# EnguinoAuxDisplaySchematic.net
KiCad netlist of a schematic drawn in EAGLE
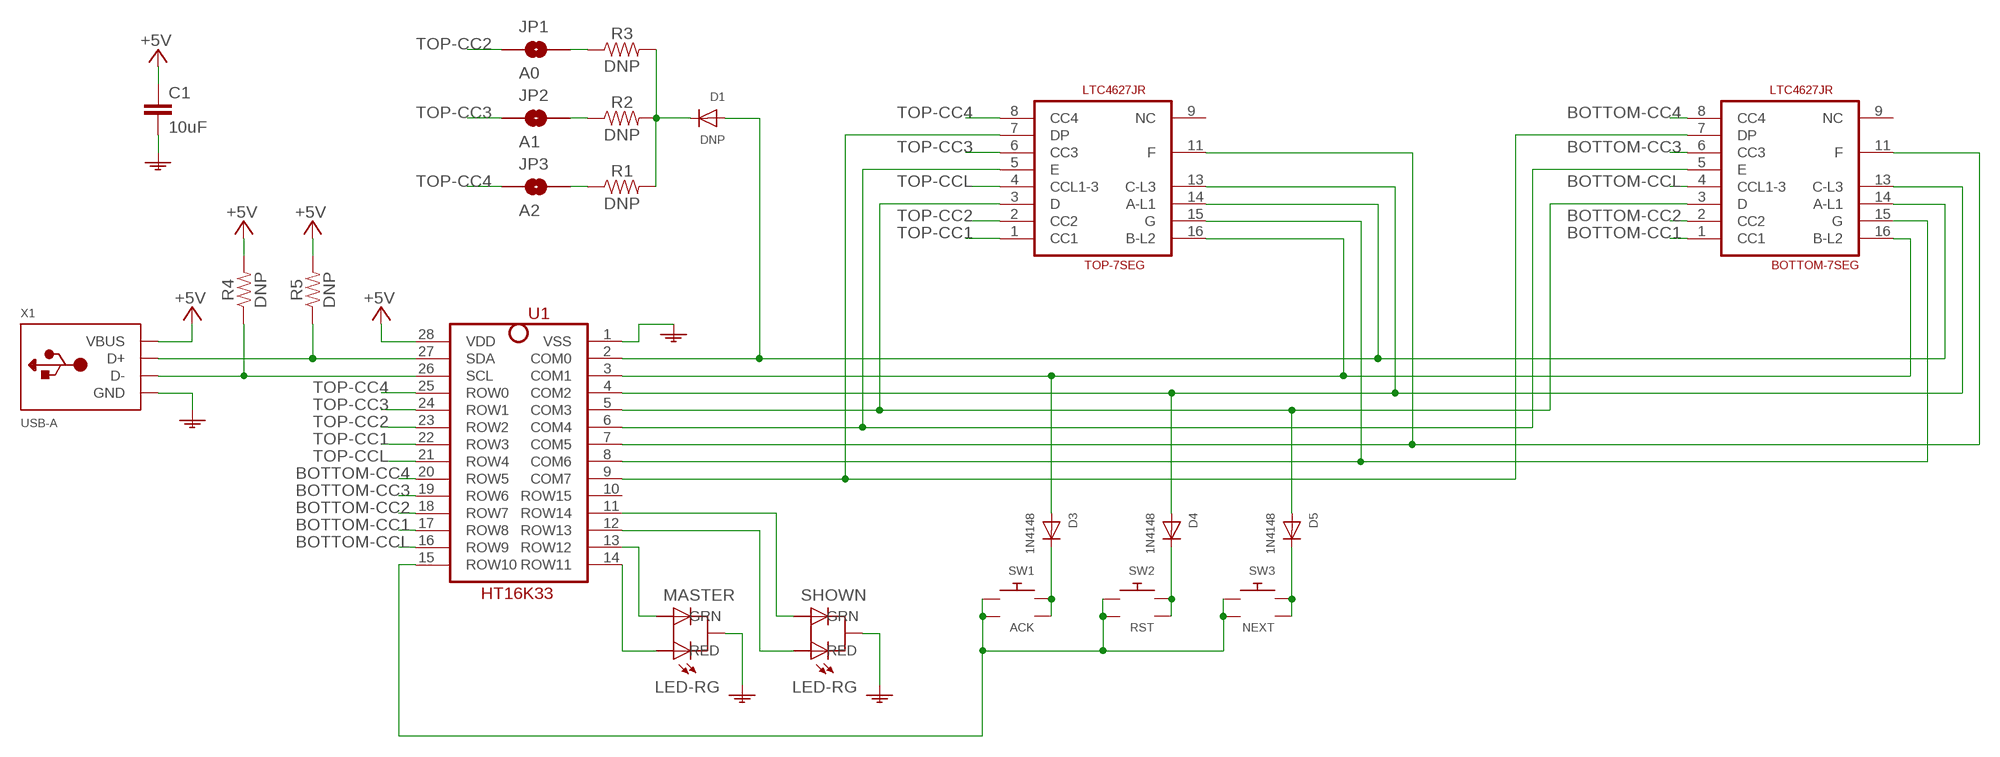
[diagram p0: schematic, sheet 1]

(export (version "E")
  (design (tool "Eeschema 10.0.6"))
  (components
    (comp (ref "BOTTOM-7SEG")
      (value "LTC4627JR")
      (footprint "eagle-import:7SEG-LED")
      (libsource (lib "eagle-import") (part "LTC4627JR"))
    )
    (comp (ref "C1")
      (value "10uF")
      (footprint "eagle-import:0805")
      (libsource (lib "eagle-import") (part "10UF-0805-10V-10%"))
    )
    (comp (ref "D1")
      (value "DNP")
      (footprint "eagle-import:SOD-123")
      (libsource (lib "eagle-import") (part "DIODESOD-123"))
    )
    (comp (ref "D3")
      (value "1N4148")
      (footprint "eagle-import:SOD-123")
      (libsource (lib "eagle-import") (part "DIODESOD-123"))
    )
    (comp (ref "D4")
      (value "1N4148")
      (footprint "eagle-import:SOD-123")
      (libsource (lib "eagle-import") (part "DIODESOD-123"))
    )
    (comp (ref "D5")
      (value "1N4148")
      (footprint "eagle-import:SOD-123")
      (libsource (lib "eagle-import") (part "DIODESOD-123"))
    )
    (comp (ref "JP1")
      (value "A0")
      (footprint "eagle-import:SMT-JUMPER_2_NO_SILK")
      (libsource (lib "eagle-import") (part "JUMPER-SMT_2_NO_SILK"))
    )
    (comp (ref "JP2")
      (value "A1")
      (footprint "eagle-import:SMT-JUMPER_2_NO_SILK")
      (libsource (lib "eagle-import") (part "JUMPER-SMT_2_NO_SILK"))
    )
    (comp (ref "JP3")
      (value "A2")
      (footprint "eagle-import:SMT-JUMPER_2_NO_SILK")
      (libsource (lib "eagle-import") (part "JUMPER-SMT_2_NO_SILK"))
    )
    (comp (ref "MASTER")
      (value "LED-RG")
      (footprint "eagle-import:LED-2-5MM")
      (libsource (lib "eagle-import") (part "LED-RG"))
    )
    (comp (ref "R1")
      (value "DNP")
      (footprint "eagle-import:0603")
      (libsource (lib "eagle-import") (part "47KOHM-0603-1/10W-1%"))
    )
    (comp (ref "R2")
      (value "DNP")
      (footprint "eagle-import:0603")
      (libsource (lib "eagle-import") (part "47KOHM-0603-1/10W-1%"))
    )
    (comp (ref "R3")
      (value "DNP")
      (footprint "eagle-import:0603")
      (libsource (lib "eagle-import") (part "47KOHM-0603-1/10W-1%"))
    )
    (comp (ref "R4")
      (value "DNP")
      (footprint "eagle-import:0603")
      (libsource (lib "eagle-import") (part "22KOHM-0603-1/10W-1%"))
    )
    (comp (ref "R5")
      (value "DNP")
      (footprint "eagle-import:0603")
      (libsource (lib "eagle-import") (part "22KOHM-0603-1/10W-1%"))
    )
    (comp (ref "SHOWN")
      (value "LED-RG")
      (footprint "eagle-import:LED-2-5MM")
      (libsource (lib "eagle-import") (part "LED-RG"))
    )
    (comp (ref "SW1")
      (value "ACK")
      (footprint "eagle-import:BUTTON-TH")
      (libsource (lib "eagle-import") (part "PUSHBUTTON"))
    )
    (comp (ref "SW2")
      (value "RST")
      (footprint "eagle-import:BUTTON-TH")
      (libsource (lib "eagle-import") (part "PUSHBUTTON"))
    )
    (comp (ref "SW3")
      (value "NEXT")
      (footprint "eagle-import:BUTTON-TH")
      (libsource (lib "eagle-import") (part "PUSHBUTTON"))
    )
    (comp (ref "TOP-7SEG")
      (value "LTC4627JR")
      (footprint "eagle-import:7SEG-LED")
      (libsource (lib "eagle-import") (part "LTC4627JR"))
    )
    (comp (ref "U1")
      (value "HT16K33")
      (footprint "eagle-import:SOP28")
      (libsource (lib "eagle-import") (part "HT16K33"))
    )
    (comp (ref "X1")
      (value "USB-A")
      (footprint "eagle-import:USB-A-AMPHENOL")
      (libsource (lib "eagle-import") (part "USB-A"))
    )
  )
  (nets
    (net (code "1") (name "+5V") (class "Default")
      (node (ref "C1") (pin "1") (pinfunction "1_1") (pintype "passive"))
      (node (ref "R4") (pin "2") (pinfunction "2_2") (pintype "passive"))
      (node (ref "R5") (pin "2") (pinfunction "2_2") (pintype "passive"))
      (node (ref "U1") (pin "28") (pinfunction "VDD_28") (pintype "power_in"))
      (node (ref "X1") (pin "P$1") (pinfunction "VBUS_P$1") (pintype "power_in"))
    )
    (net (code "2") (name "/BOTTOM-CC1") (class "Default")
      (node (ref "BOTTOM-7SEG") (pin "1") (pinfunction "CC1_1") (pintype "bidirectional"))
      (node (ref "U1") (pin "17") (pinfunction "ROW8_17") (pintype "bidirectional"))
    )
    (net (code "3") (name "/BOTTOM-CC2") (class "Default")
      (node (ref "BOTTOM-7SEG") (pin "2") (pinfunction "CC2_2") (pintype "bidirectional"))
      (node (ref "U1") (pin "18") (pinfunction "ROW7_18") (pintype "bidirectional"))
    )
    (net (code "4") (name "/BOTTOM-CC3") (class "Default")
      (node (ref "BOTTOM-7SEG") (pin "6") (pinfunction "CC3_6") (pintype "bidirectional"))
      (node (ref "U1") (pin "19") (pinfunction "ROW6_19") (pintype "bidirectional"))
    )
    (net (code "5") (name "/BOTTOM-CC4") (class "Default")
      (node (ref "BOTTOM-7SEG") (pin "8") (pinfunction "CC4_8") (pintype "bidirectional"))
      (node (ref "U1") (pin "20") (pinfunction "ROW5_20") (pintype "bidirectional"))
    )
    (net (code "6") (name "/BOTTOM-CCL") (class "Default")
      (node (ref "BOTTOM-7SEG") (pin "4") (pinfunction "CCL1-3_4") (pintype "bidirectional"))
      (node (ref "U1") (pin "16") (pinfunction "ROW9_16") (pintype "bidirectional"))
    )
    (net (code "7") (name "/TOP-CC1") (class "Default")
      (node (ref "TOP-7SEG") (pin "1") (pinfunction "CC1_1") (pintype "bidirectional"))
      (node (ref "U1") (pin "22") (pinfunction "ROW3_22") (pintype "bidirectional"))
    )
    (net (code "8") (name "/TOP-CC2") (class "Default")
      (node (ref "JP1") (pin "1") (pinfunction "1_1") (pintype "passive"))
      (node (ref "TOP-7SEG") (pin "2") (pinfunction "CC2_2") (pintype "bidirectional"))
      (node (ref "U1") (pin "23") (pinfunction "ROW2_23") (pintype "bidirectional"))
    )
    (net (code "9") (name "/TOP-CC3") (class "Default")
      (node (ref "JP2") (pin "1") (pinfunction "1_1") (pintype "passive"))
      (node (ref "TOP-7SEG") (pin "6") (pinfunction "CC3_6") (pintype "bidirectional"))
      (node (ref "U1") (pin "24") (pinfunction "ROW1_24") (pintype "bidirectional"))
    )
    (net (code "10") (name "/TOP-CC4") (class "Default")
      (node (ref "JP3") (pin "1") (pinfunction "1_1") (pintype "passive"))
      (node (ref "TOP-7SEG") (pin "8") (pinfunction "CC4_8") (pintype "bidirectional"))
      (node (ref "U1") (pin "25") (pinfunction "ROW0_25") (pintype "bidirectional"))
    )
    (net (code "11") (name "/TOP-CCL") (class "Default")
      (node (ref "TOP-7SEG") (pin "4") (pinfunction "CCL1-3_4") (pintype "bidirectional"))
      (node (ref "U1") (pin "21") (pinfunction "ROW4_21") (pintype "bidirectional"))
    )
    (net (code "12") (name "0V") (class "Default")
      (node (ref "C1") (pin "2") (pinfunction "2_2") (pintype "passive"))
      (node (ref "MASTER") (pin "2") (pinfunction "CC_2") (pintype "passive"))
      (node (ref "SHOWN") (pin "2") (pinfunction "CC_2") (pintype "passive"))
      (node (ref "U1") (pin "1") (pinfunction "VSS_1") (pintype "power_in"))
      (node (ref "X1") (pin "P$4") (pinfunction "GND_P$4") (pintype "power_in"))
    )
    (net (code "13") (name "Net-(BOTTOM-7SEG-A-L1)") (class "Default")
      (node (ref "BOTTOM-7SEG") (pin "14") (pinfunction "A-L1_14") (pintype "bidirectional"))
      (node (ref "D1") (pin "A") (pinfunction "A_A") (pintype "passive"))
      (node (ref "TOP-7SEG") (pin "14") (pinfunction "A-L1_14") (pintype "bidirectional"))
      (node (ref "U1") (pin "2") (pinfunction "COM0_2") (pintype "bidirectional"))
    )
    (net (code "14") (name "Net-(BOTTOM-7SEG-B-L2)") (class "Default")
      (node (ref "BOTTOM-7SEG") (pin "16") (pinfunction "B-L2_16") (pintype "bidirectional"))
      (node (ref "D3") (pin "A") (pinfunction "A_A") (pintype "passive"))
      (node (ref "TOP-7SEG") (pin "16") (pinfunction "B-L2_16") (pintype "bidirectional"))
      (node (ref "U1") (pin "3") (pinfunction "COM1_3") (pintype "bidirectional"))
    )
    (net (code "15") (name "Net-(BOTTOM-7SEG-C-L3)") (class "Default")
      (node (ref "BOTTOM-7SEG") (pin "13") (pinfunction "C-L3_13") (pintype "bidirectional"))
      (node (ref "D4") (pin "A") (pinfunction "A_A") (pintype "passive"))
      (node (ref "TOP-7SEG") (pin "13") (pinfunction "C-L3_13") (pintype "bidirectional"))
      (node (ref "U1") (pin "4") (pinfunction "COM2_4") (pintype "bidirectional"))
    )
    (net (code "16") (name "Net-(BOTTOM-7SEG-D)") (class "Default")
      (node (ref "BOTTOM-7SEG") (pin "3") (pinfunction "D_3") (pintype "bidirectional"))
      (node (ref "D5") (pin "A") (pinfunction "A_A") (pintype "passive"))
      (node (ref "TOP-7SEG") (pin "3") (pinfunction "D_3") (pintype "bidirectional"))
      (node (ref "U1") (pin "5") (pinfunction "COM3_5") (pintype "bidirectional"))
    )
    (net (code "17") (name "Net-(BOTTOM-7SEG-DP)") (class "Default")
      (node (ref "BOTTOM-7SEG") (pin "7") (pinfunction "DP_7") (pintype "bidirectional"))
      (node (ref "TOP-7SEG") (pin "7") (pinfunction "DP_7") (pintype "bidirectional"))
      (node (ref "U1") (pin "9") (pinfunction "COM7_9") (pintype "bidirectional"))
    )
    (net (code "18") (name "Net-(BOTTOM-7SEG-E)") (class "Default")
      (node (ref "BOTTOM-7SEG") (pin "5") (pinfunction "E_5") (pintype "bidirectional"))
      (node (ref "TOP-7SEG") (pin "5") (pinfunction "E_5") (pintype "bidirectional"))
      (node (ref "U1") (pin "6") (pinfunction "COM4_6") (pintype "bidirectional"))
    )
    (net (code "19") (name "Net-(BOTTOM-7SEG-F)") (class "Default")
      (node (ref "BOTTOM-7SEG") (pin "11") (pinfunction "F_11") (pintype "bidirectional"))
      (node (ref "TOP-7SEG") (pin "11") (pinfunction "F_11") (pintype "bidirectional"))
      (node (ref "U1") (pin "7") (pinfunction "COM5_7") (pintype "bidirectional"))
    )
    (net (code "20") (name "Net-(BOTTOM-7SEG-G)") (class "Default")
      (node (ref "BOTTOM-7SEG") (pin "15") (pinfunction "G_15") (pintype "bidirectional"))
      (node (ref "TOP-7SEG") (pin "15") (pinfunction "G_15") (pintype "bidirectional"))
      (node (ref "U1") (pin "8") (pinfunction "COM6_8") (pintype "bidirectional"))
    )
    (net (code "21") (name "Net-(D1-PadC)") (class "Default")
      (node (ref "D1") (pin "C") (pinfunction "C_C") (pintype "passive"))
      (node (ref "R1") (pin "2") (pinfunction "2_2") (pintype "passive"))
      (node (ref "R2") (pin "2") (pinfunction "2_2") (pintype "passive"))
      (node (ref "R3") (pin "2") (pinfunction "2_2") (pintype "passive"))
    )
    (net (code "22") (name "Net-(D3-PadC)") (class "Default")
      (node (ref "D3") (pin "C") (pinfunction "C_C") (pintype "passive"))
      (node (ref "SW1") (pin "1") (pinfunction "1_1") (pintype "passive"))
      (node (ref "SW1") (pin "2") (pinfunction "2_2") (pintype "passive"))
    )
    (net (code "23") (name "Net-(D4-PadC)") (class "Default")
      (node (ref "D4") (pin "C") (pinfunction "C_C") (pintype "passive"))
      (node (ref "SW2") (pin "1") (pinfunction "1_1") (pintype "passive"))
      (node (ref "SW2") (pin "2") (pinfunction "2_2") (pintype "passive"))
    )
    (net (code "24") (name "Net-(D5-PadC)") (class "Default")
      (node (ref "D5") (pin "C") (pinfunction "C_C") (pintype "passive"))
      (node (ref "SW3") (pin "1") (pinfunction "1_1") (pintype "passive"))
      (node (ref "SW3") (pin "2") (pinfunction "2_2") (pintype "passive"))
    )
    (net (code "25") (name "Net-(JP1-Pad2)") (class "Default")
      (node (ref "JP1") (pin "2") (pinfunction "2_2") (pintype "passive"))
      (node (ref "R3") (pin "1") (pinfunction "1_1") (pintype "passive"))
    )
    (net (code "26") (name "Net-(JP2-Pad2)") (class "Default")
      (node (ref "JP2") (pin "2") (pinfunction "2_2") (pintype "passive"))
      (node (ref "R2") (pin "1") (pinfunction "1_1") (pintype "passive"))
    )
    (net (code "27") (name "Net-(JP3-Pad2)") (class "Default")
      (node (ref "JP3") (pin "2") (pinfunction "2_2") (pintype "passive"))
      (node (ref "R1") (pin "1") (pinfunction "1_1") (pintype "passive"))
    )
    (net (code "28") (name "Net-(MASTER-GRN)") (class "Default")
      (node (ref "MASTER") (pin "3") (pinfunction "GRN_3") (pintype "passive"))
      (node (ref "U1") (pin "13") (pinfunction "ROW12_13") (pintype "bidirectional"))
    )
    (net (code "29") (name "Net-(MASTER-RED)") (class "Default")
      (node (ref "MASTER") (pin "1") (pinfunction "RED_1") (pintype "passive"))
      (node (ref "U1") (pin "14") (pinfunction "ROW11_14") (pintype "bidirectional"))
    )
    (net (code "30") (name "Net-(SHOWN-GRN)") (class "Default")
      (node (ref "SHOWN") (pin "3") (pinfunction "GRN_3") (pintype "passive"))
      (node (ref "U1") (pin "11") (pinfunction "ROW14_11") (pintype "bidirectional"))
    )
    (net (code "31") (name "Net-(SHOWN-RED)") (class "Default")
      (node (ref "SHOWN") (pin "1") (pinfunction "RED_1") (pintype "passive"))
      (node (ref "U1") (pin "12") (pinfunction "ROW13_12") (pintype "bidirectional"))
    )
    (net (code "32") (name "Net-(U1-ROW10)") (class "Default")
      (node (ref "SW1") (pin "3") (pinfunction "3_3") (pintype "passive"))
      (node (ref "SW1") (pin "4") (pinfunction "4_4") (pintype "passive"))
      (node (ref "SW2") (pin "3") (pinfunction "3_3") (pintype "passive"))
      (node (ref "SW2") (pin "4") (pinfunction "4_4") (pintype "passive"))
      (node (ref "SW3") (pin "3") (pinfunction "3_3") (pintype "passive"))
      (node (ref "SW3") (pin "4") (pinfunction "4_4") (pintype "passive"))
      (node (ref "U1") (pin "15") (pinfunction "ROW10_15") (pintype "bidirectional"))
    )
    (net (code "33") (name "Net-(U1-SCL)") (class "Default")
      (node (ref "R4") (pin "1") (pinfunction "1_1") (pintype "passive"))
      (node (ref "U1") (pin "26") (pinfunction "SCL_26") (pintype "bidirectional"))
      (node (ref "X1") (pin "P$2") (pinfunction "D-_P$2") (pintype "bidirectional"))
    )
    (net (code "34") (name "Net-(U1-SDA)") (class "Default")
      (node (ref "R5") (pin "1") (pinfunction "1_1") (pintype "passive"))
      (node (ref "U1") (pin "27") (pinfunction "SDA_27") (pintype "bidirectional"))
      (node (ref "X1") (pin "P$3") (pinfunction "D+_P$3") (pintype "bidirectional"))
    )
    (net (code "35") (name "unconnected-(BOTTOM-7SEG-NC-Pad9)") (class "Default")
      (node (ref "BOTTOM-7SEG") (pin "9") (pinfunction "NC_9") (pintype "no_connect"))
    )
    (net (code "36") (name "unconnected-(TOP-7SEG-NC-Pad9)") (class "Default")
      (node (ref "TOP-7SEG") (pin "9") (pinfunction "NC_9") (pintype "no_connect"))
    )
    (net (code "37") (name "unconnected-(U1-ROW15-Pad10)") (class "Default")
      (node (ref "U1") (pin "10") (pinfunction "ROW15_10") (pintype "bidirectional"))
    )
  )
)
